# SCH_Krishveer_s-OsuPad_2025-02-05.net
KiCad netlist of a schematic drawn in EasyEDA
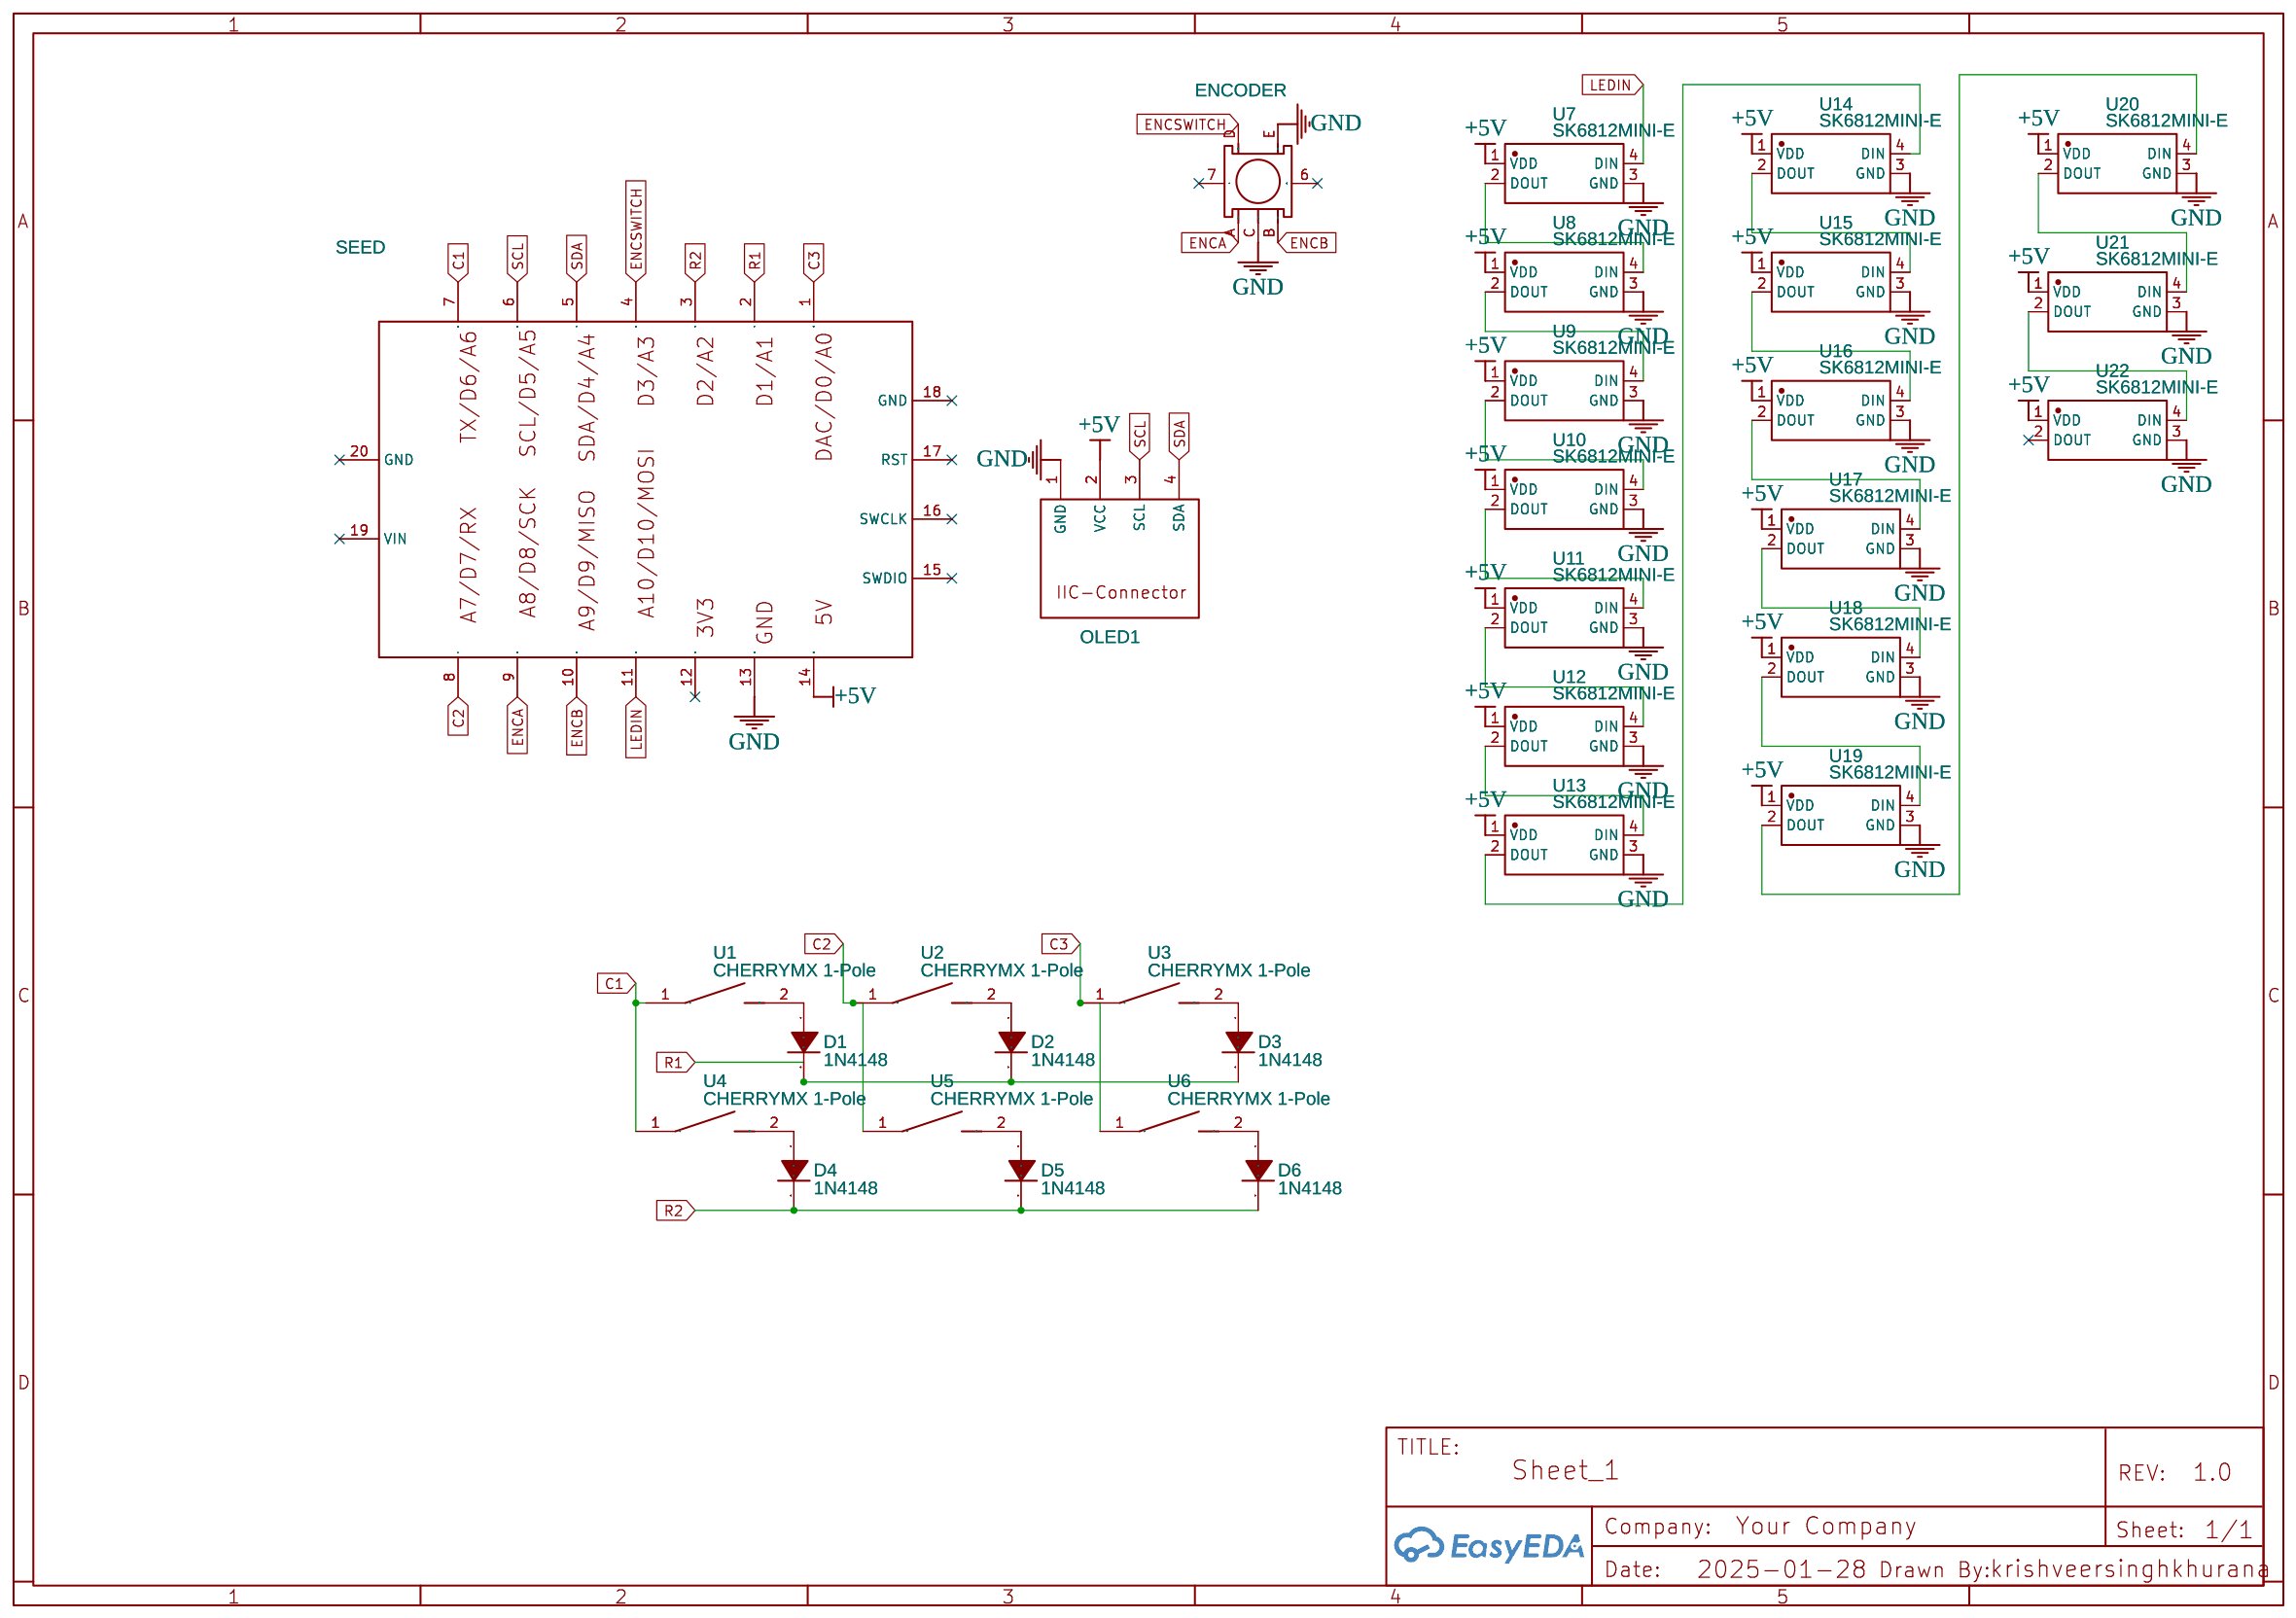
[diagram p0: schematic sheet]

(export (version "E")
  (design (tool "Eeschema 10.0.6"))
  (components
    (comp (ref "D1")
      (value "1N4148")
      (fields (field (name "Manufacturer") "ST(先科)"))
      (libsource (lib "") (part "1N4148"))
    )
    (comp (ref "D2")
      (value "1N4148")
      (fields (field (name "Manufacturer") "ST(先科)"))
      (libsource (lib "") (part "1N4148"))
    )
    (comp (ref "D3")
      (value "1N4148")
      (fields (field (name "Manufacturer") "ST(先科)"))
      (libsource (lib "") (part "1N4148"))
    )
    (comp (ref "D4")
      (value "1N4148")
      (fields (field (name "Manufacturer") "ST(先科)"))
      (libsource (lib "") (part "1N4148"))
    )
    (comp (ref "D5")
      (value "1N4148")
      (fields (field (name "Manufacturer") "ST(先科)"))
      (libsource (lib "") (part "1N4148"))
    )
    (comp (ref "D6")
      (value "1N4148")
      (fields (field (name "Manufacturer") "ST(先科)"))
      (libsource (lib "") (part "1N4148"))
    )
    (comp (ref "ENCODER")
      (value "EC11E09244AQ")
      (fields (field (name "Manufacturer") "ALPSALPINE(阿尔卑斯阿尔派)"))
      (libsource (lib "") (part "EC11E09244AQ"))
    )
    (comp (ref "OLED1") (value "0.96OLED_4P_MODULE_JX") (libsource (lib "") (part "0.96OLED_4P_MODULE_JX")))
    (comp (ref "SEED")
      (value "Seeed XIAO RP2040 ALL PINS")
      (fields (field (name "Manufacturer Part") "102010328") (field (name "Manufacturer") "Seeedstudio"))
      (libsource (lib "") (part "Seeed XIAO RP2040 ALL PINS"))
    )
    (comp (ref "U1")
      (value "CHERRYMX 1-Pole")
      (fields (field (name "Manufacturer Part") "Red RGB") (field (name "Manufacturer") "CHERRY MX"))
      (libsource (lib "") (part "CHERRYMX 1-Pole"))
    )
    (comp (ref "U2")
      (value "CHERRYMX 1-Pole")
      (fields (field (name "Manufacturer Part") "Red RGB") (field (name "Manufacturer") "CHERRY MX"))
      (libsource (lib "") (part "CHERRYMX 1-Pole"))
    )
    (comp (ref "U3")
      (value "CHERRYMX 1-Pole")
      (fields (field (name "Manufacturer Part") "Red RGB") (field (name "Manufacturer") "CHERRY MX"))
      (libsource (lib "") (part "CHERRYMX 1-Pole"))
    )
    (comp (ref "U4")
      (value "CHERRYMX 1-Pole")
      (fields (field (name "Manufacturer Part") "Red RGB") (field (name "Manufacturer") "CHERRY MX"))
      (libsource (lib "") (part "CHERRYMX 1-Pole"))
    )
    (comp (ref "U5")
      (value "CHERRYMX 1-Pole")
      (fields (field (name "Manufacturer Part") "Red RGB") (field (name "Manufacturer") "CHERRY MX"))
      (libsource (lib "") (part "CHERRYMX 1-Pole"))
    )
    (comp (ref "U6")
      (value "CHERRYMX 1-Pole")
      (fields (field (name "Manufacturer Part") "Red RGB") (field (name "Manufacturer") "CHERRY MX"))
      (libsource (lib "") (part "CHERRYMX 1-Pole"))
    )
    (comp (ref "U7") (value "SK6812MINI-E") (libsource (lib "") (part "SK6812MINI-E")))
    (comp (ref "U8") (value "SK6812MINI-E") (libsource (lib "") (part "SK6812MINI-E")))
    (comp (ref "U9") (value "SK6812MINI-E") (libsource (lib "") (part "SK6812MINI-E")))
    (comp (ref "U10") (value "SK6812MINI-E") (libsource (lib "") (part "SK6812MINI-E")))
    (comp (ref "U11") (value "SK6812MINI-E") (libsource (lib "") (part "SK6812MINI-E")))
    (comp (ref "U12") (value "SK6812MINI-E") (libsource (lib "") (part "SK6812MINI-E")))
    (comp (ref "U13") (value "SK6812MINI-E") (libsource (lib "") (part "SK6812MINI-E")))
    (comp (ref "U14") (value "SK6812MINI-E") (libsource (lib "") (part "SK6812MINI-E")))
    (comp (ref "U15") (value "SK6812MINI-E") (libsource (lib "") (part "SK6812MINI-E")))
    (comp (ref "U16") (value "SK6812MINI-E") (libsource (lib "") (part "SK6812MINI-E")))
    (comp (ref "U17") (value "SK6812MINI-E") (libsource (lib "") (part "SK6812MINI-E")))
    (comp (ref "U18") (value "SK6812MINI-E") (libsource (lib "") (part "SK6812MINI-E")))
    (comp (ref "U19") (value "SK6812MINI-E") (libsource (lib "") (part "SK6812MINI-E")))
    (comp (ref "U20") (value "SK6812MINI-E") (libsource (lib "") (part "SK6812MINI-E")))
    (comp (ref "U21") (value "SK6812MINI-E") (libsource (lib "") (part "SK6812MINI-E")))
    (comp (ref "U22") (value "SK6812MINI-E") (libsource (lib "") (part "SK6812MINI-E")))
  )
  (nets
    (net (code "1") (name "+5V") (class "Default")
      (node (ref "OLED1") (pin "2") (pinfunction "VCC_2") (pintype "unspecified"))
      (node (ref "SEED") (pin "14") (pinfunction "13_14") (pintype "unspecified"))
      (node (ref "U10") (pin "1") (pinfunction "VDD_1") (pintype "unspecified"))
      (node (ref "U11") (pin "1") (pinfunction "VDD_1") (pintype "unspecified"))
      (node (ref "U12") (pin "1") (pinfunction "VDD_1") (pintype "unspecified"))
      (node (ref "U13") (pin "1") (pinfunction "VDD_1") (pintype "unspecified"))
      (node (ref "U14") (pin "1") (pinfunction "VDD_1") (pintype "unspecified"))
      (node (ref "U15") (pin "1") (pinfunction "VDD_1") (pintype "unspecified"))
      (node (ref "U16") (pin "1") (pinfunction "VDD_1") (pintype "unspecified"))
      (node (ref "U17") (pin "1") (pinfunction "VDD_1") (pintype "unspecified"))
      (node (ref "U18") (pin "1") (pinfunction "VDD_1") (pintype "unspecified"))
      (node (ref "U19") (pin "1") (pinfunction "VDD_1") (pintype "unspecified"))
      (node (ref "U20") (pin "1") (pinfunction "VDD_1") (pintype "unspecified"))
      (node (ref "U21") (pin "1") (pinfunction "VDD_1") (pintype "unspecified"))
      (node (ref "U22") (pin "1") (pinfunction "VDD_1") (pintype "unspecified"))
      (node (ref "U7") (pin "1") (pinfunction "VDD_1") (pintype "unspecified"))
      (node (ref "U8") (pin "1") (pinfunction "VDD_1") (pintype "unspecified"))
      (node (ref "U9") (pin "1") (pinfunction "VDD_1") (pintype "unspecified"))
    )
    (net (code "2") (name "C1") (class "Default")
      (node (ref "SEED") (pin "7") (pinfunction "6_7") (pintype "unspecified"))
      (node (ref "U1") (pin "1") (pinfunction "1_1") (pintype "unspecified"))
      (node (ref "U4") (pin "1") (pinfunction "1_1") (pintype "unspecified"))
    )
    (net (code "3") (name "C2") (class "Default")
      (node (ref "SEED") (pin "8") (pinfunction "7_8") (pintype "unspecified"))
      (node (ref "U2") (pin "1") (pinfunction "1_1") (pintype "unspecified"))
      (node (ref "U5") (pin "1") (pinfunction "1_1") (pintype "unspecified"))
    )
    (net (code "4") (name "C3") (class "Default")
      (node (ref "SEED") (pin "1") (pinfunction "0_1") (pintype "unspecified"))
      (node (ref "U3") (pin "1") (pinfunction "1_1") (pintype "unspecified"))
      (node (ref "U6") (pin "1") (pinfunction "1_1") (pintype "unspecified"))
    )
    (net (code "5") (name "ENCA") (class "Default")
      (node (ref "ENCODER") (pin "A") (pinfunction "A_A") (pintype "unspecified"))
      (node (ref "SEED") (pin "9") (pinfunction "8_9") (pintype "unspecified"))
    )
    (net (code "6") (name "ENCB") (class "Default")
      (node (ref "ENCODER") (pin "B") (pinfunction "B_B") (pintype "unspecified"))
      (node (ref "SEED") (pin "10") (pinfunction "9_10") (pintype "unspecified"))
    )
    (net (code "7") (name "ENCSWITCH") (class "Default")
      (node (ref "ENCODER") (pin "D") (pinfunction "D_D") (pintype "unspecified"))
      (node (ref "SEED") (pin "4") (pinfunction "3_4") (pintype "unspecified"))
    )
    (net (code "8") (name "GND") (class "Default")
      (node (ref "ENCODER") (pin "C") (pinfunction "C_C") (pintype "unspecified"))
      (node (ref "ENCODER") (pin "E") (pinfunction "E_E") (pintype "unspecified"))
      (node (ref "OLED1") (pin "1") (pinfunction "GND_1") (pintype "unspecified"))
      (node (ref "SEED") (pin "13") (pinfunction "12_13") (pintype "unspecified"))
      (node (ref "U10") (pin "3") (pinfunction "GND_3") (pintype "unspecified"))
      (node (ref "U11") (pin "3") (pinfunction "GND_3") (pintype "unspecified"))
      (node (ref "U12") (pin "3") (pinfunction "GND_3") (pintype "unspecified"))
      (node (ref "U13") (pin "3") (pinfunction "GND_3") (pintype "unspecified"))
      (node (ref "U14") (pin "3") (pinfunction "GND_3") (pintype "unspecified"))
      (node (ref "U15") (pin "3") (pinfunction "GND_3") (pintype "unspecified"))
      (node (ref "U16") (pin "3") (pinfunction "GND_3") (pintype "unspecified"))
      (node (ref "U17") (pin "3") (pinfunction "GND_3") (pintype "unspecified"))
      (node (ref "U18") (pin "3") (pinfunction "GND_3") (pintype "unspecified"))
      (node (ref "U19") (pin "3") (pinfunction "GND_3") (pintype "unspecified"))
      (node (ref "U20") (pin "3") (pinfunction "GND_3") (pintype "unspecified"))
      (node (ref "U21") (pin "3") (pinfunction "GND_3") (pintype "unspecified"))
      (node (ref "U22") (pin "3") (pinfunction "GND_3") (pintype "unspecified"))
      (node (ref "U7") (pin "3") (pinfunction "GND_3") (pintype "unspecified"))
      (node (ref "U8") (pin "3") (pinfunction "GND_3") (pintype "unspecified"))
      (node (ref "U9") (pin "3") (pinfunction "GND_3") (pintype "unspecified"))
    )
    (net (code "9") (name "LEDIN") (class "Default")
      (node (ref "SEED") (pin "11") (pinfunction "10_11") (pintype "unspecified"))
      (node (ref "U7") (pin "4") (pinfunction "DIN_4") (pintype "unspecified"))
    )
    (net (code "10") (name "Net-(D1-A)") (class "Default")
      (node (ref "D1") (pin "1") (pinfunction "A_1") (pintype "unspecified"))
      (node (ref "U1") (pin "2") (pinfunction "2_2") (pintype "unspecified"))
    )
    (net (code "11") (name "Net-(D2-A)") (class "Default")
      (node (ref "D2") (pin "1") (pinfunction "A_1") (pintype "unspecified"))
      (node (ref "U2") (pin "2") (pinfunction "2_2") (pintype "unspecified"))
    )
    (net (code "12") (name "Net-(D3-A)") (class "Default")
      (node (ref "D3") (pin "1") (pinfunction "A_1") (pintype "unspecified"))
      (node (ref "U3") (pin "2") (pinfunction "2_2") (pintype "unspecified"))
    )
    (net (code "13") (name "Net-(D4-A)") (class "Default")
      (node (ref "D4") (pin "1") (pinfunction "A_1") (pintype "unspecified"))
      (node (ref "U4") (pin "2") (pinfunction "2_2") (pintype "unspecified"))
    )
    (net (code "14") (name "Net-(D5-A)") (class "Default")
      (node (ref "D5") (pin "1") (pinfunction "A_1") (pintype "unspecified"))
      (node (ref "U5") (pin "2") (pinfunction "2_2") (pintype "unspecified"))
    )
    (net (code "15") (name "Net-(D6-A)") (class "Default")
      (node (ref "D6") (pin "1") (pinfunction "A_1") (pintype "unspecified"))
      (node (ref "U6") (pin "2") (pinfunction "2_2") (pintype "unspecified"))
    )
    (net (code "16") (name "Net-(U7-DOUT)") (class "Default")
      (node (ref "U7") (pin "2") (pinfunction "DOUT_2") (pintype "unspecified"))
      (node (ref "U8") (pin "4") (pinfunction "DIN_4") (pintype "unspecified"))
    )
    (net (code "17") (name "Net-(U8-DOUT)") (class "Default")
      (node (ref "U8") (pin "2") (pinfunction "DOUT_2") (pintype "unspecified"))
      (node (ref "U9") (pin "4") (pinfunction "DIN_4") (pintype "unspecified"))
    )
    (net (code "18") (name "Net-(U10-DIN)") (class "Default")
      (node (ref "U10") (pin "4") (pinfunction "DIN_4") (pintype "unspecified"))
      (node (ref "U9") (pin "2") (pinfunction "DOUT_2") (pintype "unspecified"))
    )
    (net (code "19") (name "Net-(U10-DOUT)") (class "Default")
      (node (ref "U10") (pin "2") (pinfunction "DOUT_2") (pintype "unspecified"))
      (node (ref "U11") (pin "4") (pinfunction "DIN_4") (pintype "unspecified"))
    )
    (net (code "20") (name "Net-(U11-DOUT)") (class "Default")
      (node (ref "U11") (pin "2") (pinfunction "DOUT_2") (pintype "unspecified"))
      (node (ref "U12") (pin "4") (pinfunction "DIN_4") (pintype "unspecified"))
    )
    (net (code "21") (name "Net-(U12-DOUT)") (class "Default")
      (node (ref "U12") (pin "2") (pinfunction "DOUT_2") (pintype "unspecified"))
      (node (ref "U13") (pin "4") (pinfunction "DIN_4") (pintype "unspecified"))
    )
    (net (code "22") (name "Net-(U13-DOUT)") (class "Default")
      (node (ref "U13") (pin "2") (pinfunction "DOUT_2") (pintype "unspecified"))
      (node (ref "U14") (pin "4") (pinfunction "DIN_4") (pintype "unspecified"))
    )
    (net (code "23") (name "Net-(U14-DOUT)") (class "Default")
      (node (ref "U14") (pin "2") (pinfunction "DOUT_2") (pintype "unspecified"))
      (node (ref "U15") (pin "4") (pinfunction "DIN_4") (pintype "unspecified"))
    )
    (net (code "24") (name "Net-(U15-DOUT)") (class "Default")
      (node (ref "U15") (pin "2") (pinfunction "DOUT_2") (pintype "unspecified"))
      (node (ref "U16") (pin "4") (pinfunction "DIN_4") (pintype "unspecified"))
    )
    (net (code "25") (name "Net-(U16-DOUT)") (class "Default")
      (node (ref "U16") (pin "2") (pinfunction "DOUT_2") (pintype "unspecified"))
      (node (ref "U17") (pin "4") (pinfunction "DIN_4") (pintype "unspecified"))
    )
    (net (code "26") (name "Net-(U17-DOUT)") (class "Default")
      (node (ref "U17") (pin "2") (pinfunction "DOUT_2") (pintype "unspecified"))
      (node (ref "U18") (pin "4") (pinfunction "DIN_4") (pintype "unspecified"))
    )
    (net (code "27") (name "Net-(U18-DOUT)") (class "Default")
      (node (ref "U18") (pin "2") (pinfunction "DOUT_2") (pintype "unspecified"))
      (node (ref "U19") (pin "4") (pinfunction "DIN_4") (pintype "unspecified"))
    )
    (net (code "28") (name "Net-(U19-DOUT)") (class "Default")
      (node (ref "U19") (pin "2") (pinfunction "DOUT_2") (pintype "unspecified"))
      (node (ref "U20") (pin "4") (pinfunction "DIN_4") (pintype "unspecified"))
    )
    (net (code "29") (name "Net-(U20-DOUT)") (class "Default")
      (node (ref "U20") (pin "2") (pinfunction "DOUT_2") (pintype "unspecified"))
      (node (ref "U21") (pin "4") (pinfunction "DIN_4") (pintype "unspecified"))
    )
    (net (code "30") (name "Net-(U21-DOUT)") (class "Default")
      (node (ref "U21") (pin "2") (pinfunction "DOUT_2") (pintype "unspecified"))
      (node (ref "U22") (pin "4") (pinfunction "DIN_4") (pintype "unspecified"))
    )
    (net (code "31") (name "R1") (class "Default")
      (node (ref "D1") (pin "2") (pinfunction "C_2") (pintype "unspecified"))
      (node (ref "D2") (pin "2") (pinfunction "C_2") (pintype "unspecified"))
      (node (ref "D3") (pin "2") (pinfunction "C_2") (pintype "unspecified"))
      (node (ref "SEED") (pin "2") (pinfunction "1_2") (pintype "unspecified"))
    )
    (net (code "32") (name "R2") (class "Default")
      (node (ref "D4") (pin "2") (pinfunction "C_2") (pintype "unspecified"))
      (node (ref "D5") (pin "2") (pinfunction "C_2") (pintype "unspecified"))
      (node (ref "D6") (pin "2") (pinfunction "C_2") (pintype "unspecified"))
      (node (ref "SEED") (pin "3") (pinfunction "2_3") (pintype "unspecified"))
    )
    (net (code "33") (name "SCL") (class "Default")
      (node (ref "OLED1") (pin "3") (pinfunction "SCL_3") (pintype "unspecified"))
      (node (ref "SEED") (pin "6") (pinfunction "5_6") (pintype "unspecified"))
    )
    (net (code "34") (name "SDA") (class "Default")
      (node (ref "OLED1") (pin "4") (pinfunction "SDA_4") (pintype "unspecified"))
      (node (ref "SEED") (pin "5") (pinfunction "4_5") (pintype "unspecified"))
    )
    (net (code "35") (name "unconnected-(ENCODER-Pad6)") (class "Default")
      (node (ref "ENCODER") (pin "6") (pinfunction "6_6") (pintype "unspecified+no_connect"))
    )
    (net (code "36") (name "unconnected-(ENCODER-Pad7)") (class "Default")
      (node (ref "ENCODER") (pin "7") (pinfunction "7_7") (pintype "unspecified+no_connect"))
    )
    (net (code "37") (name "unconnected-(SEED-11-Pad12)") (class "Default")
      (node (ref "SEED") (pin "12") (pinfunction "11_12") (pintype "unspecified+no_connect"))
    )
    (net (code "38") (name "unconnected-(SEED-GND-Pad18)") (class "Default")
      (node (ref "SEED") (pin "18") (pinfunction "GND_18") (pintype "unspecified+no_connect"))
    )
    (net (code "39") (name "unconnected-(SEED-GND-Pad20)") (class "Default")
      (node (ref "SEED") (pin "20") (pinfunction "GND_20") (pintype "unspecified+no_connect"))
    )
    (net (code "40") (name "unconnected-(SEED-RST-Pad17)") (class "Default")
      (node (ref "SEED") (pin "17") (pinfunction "RST_17") (pintype "unspecified+no_connect"))
    )
    (net (code "41") (name "unconnected-(SEED-SWCLK-Pad16)") (class "Default")
      (node (ref "SEED") (pin "16") (pinfunction "SWCLK_16") (pintype "unspecified+no_connect"))
    )
    (net (code "42") (name "unconnected-(SEED-SWDIO-Pad15)") (class "Default")
      (node (ref "SEED") (pin "15") (pinfunction "SWDIO_15") (pintype "unspecified+no_connect"))
    )
    (net (code "43") (name "unconnected-(SEED-VIN-Pad19)") (class "Default")
      (node (ref "SEED") (pin "19") (pinfunction "VIN_19") (pintype "unspecified+no_connect"))
    )
    (net (code "44") (name "unconnected-(U22-DOUT-Pad2)") (class "Default")
      (node (ref "U22") (pin "2") (pinfunction "DOUT_2") (pintype "unspecified+no_connect"))
    )
  )
)
